# Ultrasonic.net
KiCad netlist of a schematic drawn in Altium Designer
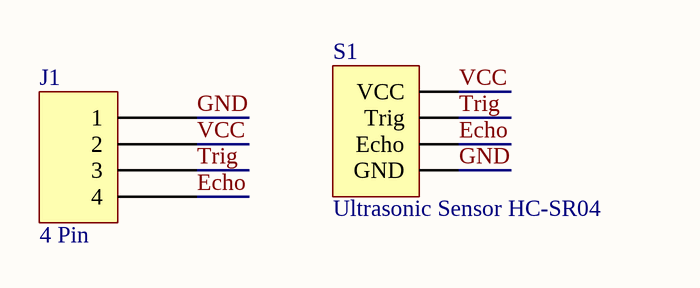
[diagram p0: Ultrasonic.SchDoc]

(export (version "E")
  (design (tool "Eeschema 10.0.6"))
  (components
    (comp (ref "J1")
      (value "4 Pin")
      (footprint "JST XH B4B-XH-A - RIGHT")
      (libsource (lib "Connectors") (part "4 Pin"))
    )
    (comp (ref "S1")
      (value "Ultrasonic Sensor HC-SR04")
      (footprint "Ultrasonic")
      (libsource (lib "Sensors") (part "Ultrasonic Sensor HC-SR04"))
    )
  )
  (nets
    (net (code "1") (name "/Echo") (class "Default")
      (node (ref "J1") (pin "4") (pinfunction "4_4") (pintype "passive"))
      (node (ref "S1") (pin "3") (pinfunction "Echo_3") (pintype "passive"))
    )
    (net (code "2") (name "/GND") (class "Default")
      (node (ref "J1") (pin "1") (pinfunction "1_1") (pintype "passive"))
      (node (ref "S1") (pin "4") (pinfunction "GND_4") (pintype "passive"))
    )
    (net (code "3") (name "/Trig") (class "Default")
      (node (ref "J1") (pin "3") (pinfunction "3_3") (pintype "passive"))
      (node (ref "S1") (pin "2") (pinfunction "Trig_2") (pintype "passive"))
    )
    (net (code "4") (name "/VCC") (class "Default")
      (node (ref "J1") (pin "2") (pinfunction "2_2") (pintype "passive"))
      (node (ref "S1") (pin "1") (pinfunction "VCC_1") (pintype "passive"))
    )
  )
)
